# opa1671.net
KiCad netlist of a schematic drawn in Altium Designer
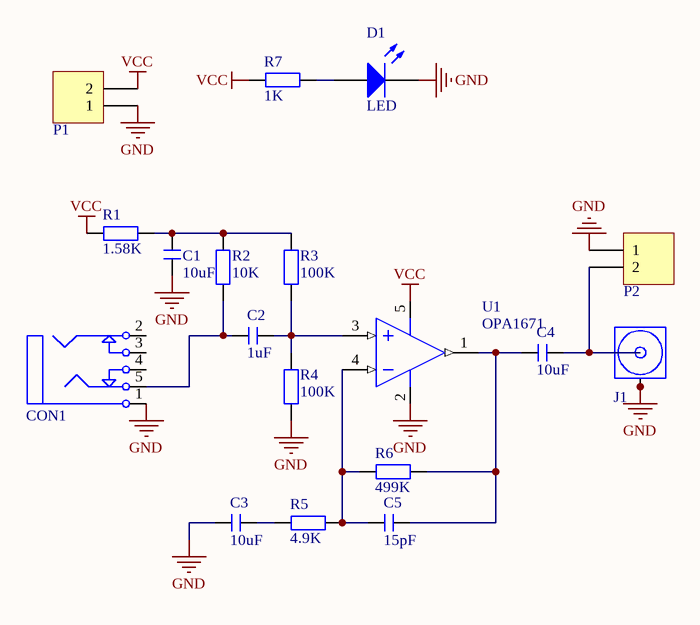
[diagram p0: opa1671音频放大.SchDoc]

(export (version "E")
  (design (tool "Eeschema 10.0.6"))
  (components
    (comp (ref "C1")
      (value "10uF")
      (footprint "C 0805")
      (description "无极性贴片电容")
      (fields (field (name "版权归属") "源创客"))
      (libsource (lib "电阻-电容-电感") (part "C"))
    )
    (comp (ref "C2")
      (value "1uF")
      (footprint "C 0805")
      (description "无极性贴片电容")
      (fields (field (name "版权归属") "源创客"))
      (libsource (lib "电阻-电容-电感") (part "C"))
    )
    (comp (ref "C3")
      (value "10uF")
      (footprint "C 0805")
      (description "无极性贴片电容")
      (fields (field (name "版权归属") "源创客"))
      (libsource (lib "电阻-电容-电感") (part "C"))
    )
    (comp (ref "C4")
      (value "10uF")
      (footprint "C 0805")
      (description "无极性贴片电容")
      (fields (field (name "版权归属") "源创客"))
      (libsource (lib "电阻-电容-电感") (part "C"))
    )
    (comp (ref "C5")
      (value "15pF")
      (footprint "C 0603")
      (description "无极性贴片电容")
      (fields (field (name "版权归属") "源创客"))
      (libsource (lib "电阻-电容-电感") (part "C"))
    )
    (comp (ref "CON1")
      (value "3F07_BK")
      (footprint "3F07_BK")
      (description "3.5mm耳机插座")
      (fields (field (name "版权归属") "源创客"))
      (libsource (lib "接口类") (part "3F07"))
    )
    (comp (ref "D1")
      (value "LED")
      (footprint "LED_0805")
      (description "发光二极管")
      (fields (field (name "PUBLISHER") "Altium Limited"))
      (libsource (lib "LIB") (part "LED"))
    )
    (comp (ref "J1") (value "COAX") (footprint "MCX5.08-5-H") (libsource (lib "LIB") (part "COAX")))
    (comp (ref "P1")
      (value "Header 2")
      (footprint "HDR2X1_B2")
      (description "接插件")
      (fields (field (name "PUBLISHER") "Altium Limited"))
      (libsource (lib "LIB") (part "Header 2"))
    )
    (comp (ref "P2")
      (value "Header 2")
      (footprint "HDR2X1_A")
      (description "接插件")
      (fields (field (name "PUBLISHER") "Altium Limited"))
      (libsource (lib "") (part "Header 2_1"))
    )
    (comp (ref "R1")
      (value "1.58K")
      (footprint "R 0603")
      (description "贴片电阻")
      (fields (field (name "版权归属") "源创客"))
      (libsource (lib "电阻-电容-电感") (part "R"))
    )
    (comp (ref "R2")
      (value "10K")
      (footprint "R 0603")
      (description "贴片电阻")
      (fields (field (name "版权归属") "源创客"))
      (libsource (lib "电阻-电容-电感") (part "R"))
    )
    (comp (ref "R3")
      (value "100K")
      (footprint "R 0603")
      (description "贴片电阻")
      (fields (field (name "版权归属") "源创客"))
      (libsource (lib "电阻-电容-电感") (part "R"))
    )
    (comp (ref "R4")
      (value "100K")
      (footprint "R 0603")
      (description "贴片电阻")
      (fields (field (name "版权归属") "源创客"))
      (libsource (lib "电阻-电容-电感") (part "R"))
    )
    (comp (ref "R5")
      (value "4.9K")
      (footprint "R 0603")
      (description "贴片电阻")
      (fields (field (name "版权归属") "源创客"))
      (libsource (lib "电阻-电容-电感") (part "R"))
    )
    (comp (ref "R6")
      (value "499K")
      (footprint "R 0603")
      (description "贴片电阻")
      (fields (field (name "版权归属") "源创客"))
      (libsource (lib "电阻-电容-电感") (part "R"))
    )
    (comp (ref "R7")
      (value "1K")
      (footprint "R 0805")
      (description "贴片电阻")
      (fields (field (name "版权归属") "源创客"))
      (libsource (lib "电阻-电容-电感") (part "R"))
    )
    (comp (ref "U1")
      (value "OPA1671")
      (footprint "SC-70 5")
      (description "12MHz、低噪声、轨至轨、音频运算放大器")
      (libsource (lib "LIB") (part "opa1671"))
    )
  )
  (nets
    (net (code "1") (name "GND") (class "Default")
      (node (ref "C1") (pin "1") (pinfunction "1_1") (pintype "passive"))
      (node (ref "C3") (pin "1") (pinfunction "1_1") (pintype "passive"))
      (node (ref "CON1") (pin "1") (pinfunction "1_1") (pintype "passive"))
      (node (ref "D1") (pin "2") (pinfunction "K_2") (pintype "passive"))
      (node (ref "J1") (pin "2") (pinfunction "GND_2") (pintype "passive"))
      (node (ref "J1") (pin "3") (pinfunction "GND_3") (pintype "passive"))
      (node (ref "J1") (pin "4") (pinfunction "GND_4") (pintype "passive"))
      (node (ref "J1") (pin "5") (pinfunction "GND_5") (pintype "passive"))
      (node (ref "P1") (pin "1") (pinfunction "1_1") (pintype "passive"))
      (node (ref "P2") (pin "1") (pinfunction "1_1") (pintype "passive"))
      (node (ref "R4") (pin "2") (pinfunction "2_2") (pintype "passive"))
      (node (ref "U1") (pin "2") (pinfunction "V-_2") (pintype "power_in"))
    )
    (net (code "2") (name "Net-(C1-Pad2)") (class "Default")
      (node (ref "C1") (pin "2") (pinfunction "2_2") (pintype "passive"))
      (node (ref "R1") (pin "2") (pinfunction "2_2") (pintype "passive"))
      (node (ref "R2") (pin "1") (pinfunction "1_1") (pintype "passive"))
      (node (ref "R3") (pin "1") (pinfunction "1_1") (pintype "passive"))
    )
    (net (code "3") (name "Net-(C2-Pad1)") (class "Default")
      (node (ref "C2") (pin "1") (pinfunction "1_1") (pintype "passive"))
      (node (ref "CON1") (pin "5") (pinfunction "5_5") (pintype "passive"))
      (node (ref "R2") (pin "2") (pinfunction "2_2") (pintype "passive"))
    )
    (net (code "4") (name "Net-(C3-Pad2)") (class "Default")
      (node (ref "C3") (pin "2") (pinfunction "2_2") (pintype "passive"))
      (node (ref "R5") (pin "1") (pinfunction "1_1") (pintype "passive"))
    )
    (net (code "5") (name "Net-(D1-A)") (class "Default")
      (node (ref "D1") (pin "1") (pinfunction "A_1") (pintype "passive"))
      (node (ref "R7") (pin "2") (pinfunction "2_2") (pintype "passive"))
    )
    (net (code "6") (name "Net-(J1-Signal)") (class "Default")
      (node (ref "C4") (pin "2") (pinfunction "2_2") (pintype "passive"))
      (node (ref "J1") (pin "1") (pinfunction "Signal_1") (pintype "passive"))
      (node (ref "P2") (pin "2") (pinfunction "2_2") (pintype "passive"))
    )
    (net (code "7") (name "Net-(U1-+IN)") (class "Default")
      (node (ref "C2") (pin "2") (pinfunction "2_2") (pintype "passive"))
      (node (ref "R3") (pin "2") (pinfunction "2_2") (pintype "passive"))
      (node (ref "R4") (pin "1") (pinfunction "1_1") (pintype "passive"))
      (node (ref "U1") (pin "3") (pinfunction "+IN_3") (pintype "input"))
    )
    (net (code "8") (name "Net-(U1--IN)") (class "Default")
      (node (ref "C5") (pin "1") (pinfunction "1_1") (pintype "passive"))
      (node (ref "R5") (pin "2") (pinfunction "2_2") (pintype "passive"))
      (node (ref "R6") (pin "1") (pinfunction "1_1") (pintype "passive"))
      (node (ref "U1") (pin "4") (pinfunction "-IN_4") (pintype "input"))
    )
    (net (code "9") (name "Net-(U1-OUT)") (class "Default")
      (node (ref "C4") (pin "1") (pinfunction "1_1") (pintype "passive"))
      (node (ref "C5") (pin "2") (pinfunction "2_2") (pintype "passive"))
      (node (ref "R6") (pin "2") (pinfunction "2_2") (pintype "passive"))
      (node (ref "U1") (pin "1") (pinfunction "OUT_1") (pintype "output"))
    )
    (net (code "10") (name "VCC") (class "Default")
      (node (ref "P1") (pin "2") (pinfunction "2_2") (pintype "passive"))
      (node (ref "R1") (pin "1") (pinfunction "1_1") (pintype "passive"))
      (node (ref "R7") (pin "1") (pinfunction "1_1") (pintype "passive"))
      (node (ref "U1") (pin "5") (pinfunction "V+_5") (pintype "power_in"))
    )
    (net (code "11") (name "unconnected-(CON1-Pad2)") (class "Default")
      (node (ref "CON1") (pin "2") (pinfunction "2_2") (pintype "passive"))
    )
    (net (code "12") (name "unconnected-(CON1-Pad3)") (class "Default")
      (node (ref "CON1") (pin "3") (pinfunction "3_3") (pintype "passive"))
    )
    (net (code "13") (name "unconnected-(CON1-Pad4)") (class "Default")
      (node (ref "CON1") (pin "4") (pinfunction "4_4") (pintype "passive"))
    )
  )
)
